# 04_Light_courtains.net
KiCad netlist of a schematic drawn in Altium Designer
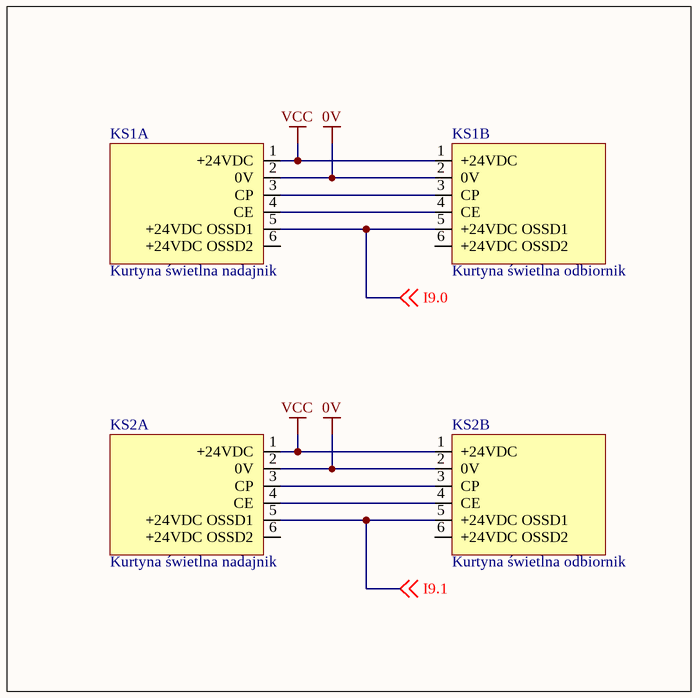
[diagram p0: [04] Light courtains.SchDoc]

(export (version "E")
  (design (tool "Eeschema 10.0.6"))
  (components
    (comp (ref "KS1A")
      (value "Kurtyna świetlna nadajnik")
      (libsource (lib "Schlib1") (part "light courtain emiter"))
    )
    (comp (ref "KS1B")
      (value "Kurtyna świetlna odbiornik")
      (libsource (lib "Schlib1") (part "light courtain receiver"))
    )
    (comp (ref "KS2A")
      (value "Kurtyna świetlna nadajnik")
      (libsource (lib "Schlib1") (part "light courtain emiter"))
    )
    (comp (ref "KS2B")
      (value "Kurtyna świetlna odbiornik")
      (libsource (lib "Schlib1") (part "light courtain receiver"))
    )
  )
  (nets
    (net (code "1") (name "0V") (class "Default")
      (node (ref "KS1A") (pin "2") (pinfunction "0V_2") (pintype "passive"))
      (node (ref "KS1B") (pin "2") (pinfunction "0V_2") (pintype "passive"))
      (node (ref "KS2A") (pin "2") (pinfunction "0V_2") (pintype "passive"))
      (node (ref "KS2B") (pin "2") (pinfunction "0V_2") (pintype "passive"))
    )
    (net (code "2") (name "I9.0") (class "Default")
      (node (ref "KS1A") (pin "5") (pinfunction "+24VDC_OSSD1_5") (pintype "passive"))
      (node (ref "KS1B") (pin "5") (pinfunction "+24VDC_OSSD1_5") (pintype "passive"))
    )
    (net (code "3") (name "I9.1") (class "Default")
      (node (ref "KS2A") (pin "5") (pinfunction "+24VDC_OSSD1_5") (pintype "passive"))
      (node (ref "KS2B") (pin "5") (pinfunction "+24VDC_OSSD1_5") (pintype "passive"))
    )
    (net (code "4") (name "Net-(KS1A-CE)") (class "Default")
      (node (ref "KS1A") (pin "4") (pinfunction "CE_4") (pintype "passive"))
      (node (ref "KS1B") (pin "4") (pinfunction "CE_4") (pintype "passive"))
    )
    (net (code "5") (name "Net-(KS1A-CP)") (class "Default")
      (node (ref "KS1A") (pin "3") (pinfunction "CP_3") (pintype "passive"))
      (node (ref "KS1B") (pin "3") (pinfunction "CP_3") (pintype "passive"))
    )
    (net (code "6") (name "Net-(KS2A-CE)") (class "Default")
      (node (ref "KS2A") (pin "4") (pinfunction "CE_4") (pintype "passive"))
      (node (ref "KS2B") (pin "4") (pinfunction "CE_4") (pintype "passive"))
    )
    (net (code "7") (name "Net-(KS2A-CP)") (class "Default")
      (node (ref "KS2A") (pin "3") (pinfunction "CP_3") (pintype "passive"))
      (node (ref "KS2B") (pin "3") (pinfunction "CP_3") (pintype "passive"))
    )
    (net (code "8") (name "VCC") (class "Default")
      (node (ref "KS1A") (pin "1") (pinfunction "+24VDC_1") (pintype "passive"))
      (node (ref "KS1B") (pin "1") (pinfunction "+24VDC_1") (pintype "passive"))
      (node (ref "KS2A") (pin "1") (pinfunction "+24VDC_1") (pintype "passive"))
      (node (ref "KS2B") (pin "1") (pinfunction "+24VDC_1") (pintype "passive"))
    )
    (net (code "9") (name "unconnected-(KS1A-+24VDC_OSSD2-Pad6)") (class "Default")
      (node (ref "KS1A") (pin "6") (pinfunction "+24VDC_OSSD2_6") (pintype "passive"))
    )
    (net (code "10") (name "unconnected-(KS1B-+24VDC_OSSD2-Pad6)") (class "Default")
      (node (ref "KS1B") (pin "6") (pinfunction "+24VDC_OSSD2_6") (pintype "passive"))
    )
    (net (code "11") (name "unconnected-(KS2A-+24VDC_OSSD2-Pad6)") (class "Default")
      (node (ref "KS2A") (pin "6") (pinfunction "+24VDC_OSSD2_6") (pintype "passive"))
    )
    (net (code "12") (name "unconnected-(KS2B-+24VDC_OSSD2-Pad6)") (class "Default")
      (node (ref "KS2B") (pin "6") (pinfunction "+24VDC_OSSD2_6") (pintype "passive"))
    )
  )
)
